# PowerOn.net
KiCad netlist of a schematic drawn in EAGLE
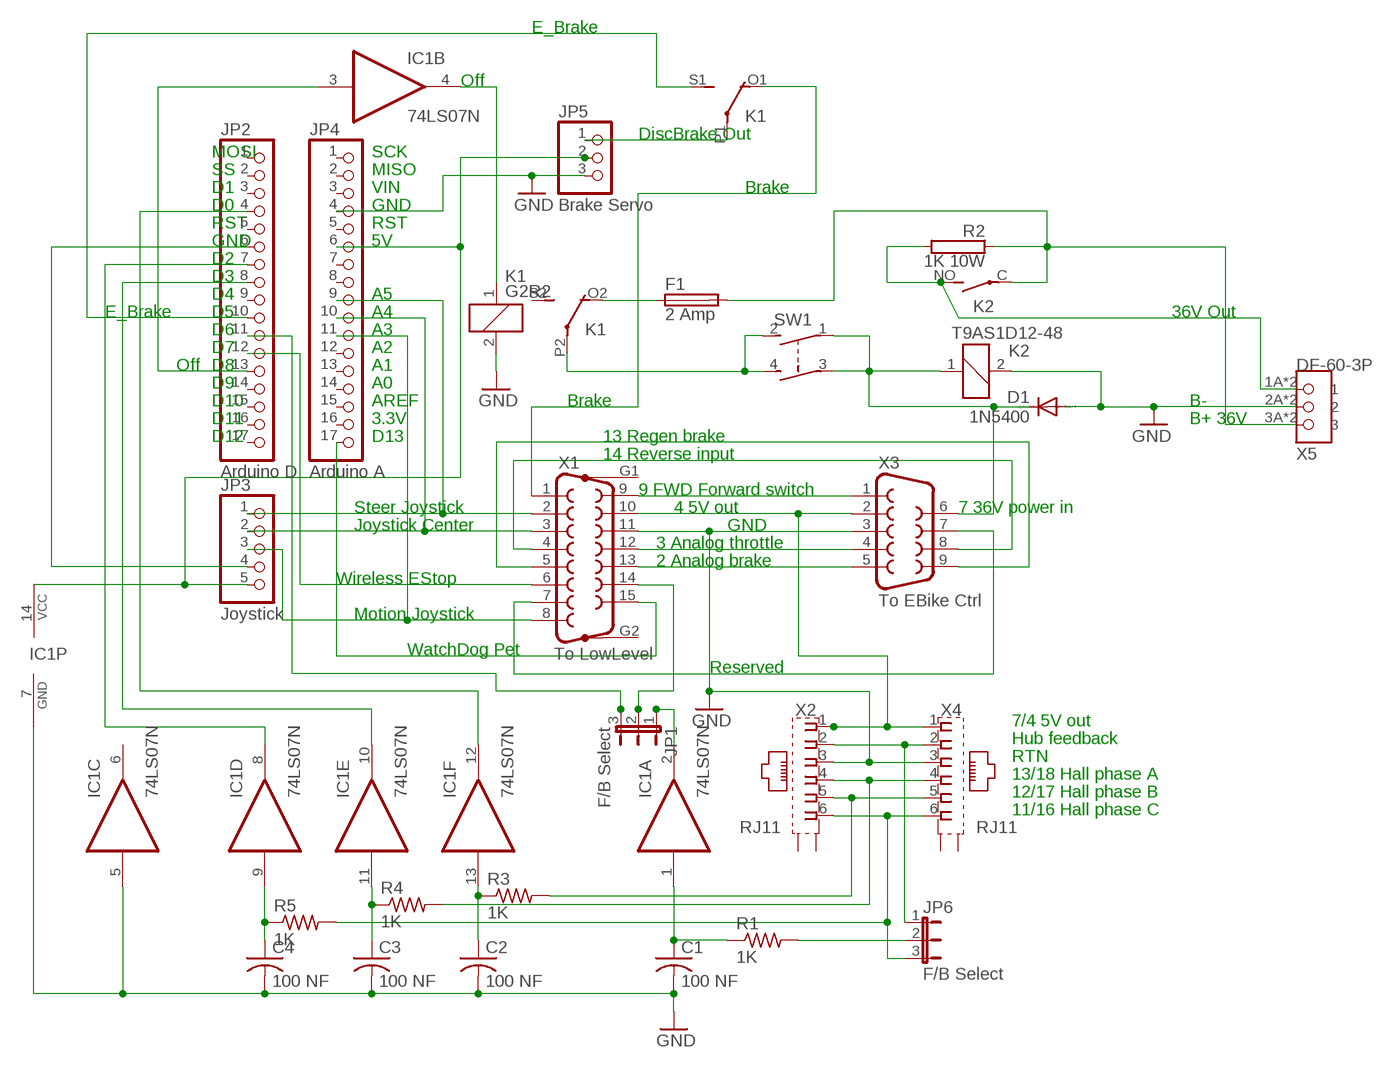
[diagram p0: schematic, sheet 1]

(export (version "E")
  (design (tool "Eeschema 10.0.6"))
  (components
    (comp (ref "C1")
      (value "100 NF")
      (footprint "eagle-import:C050-050X075")
      (libsource (lib "eagle-import") (part "C-US050-050X075"))
    )
    (comp (ref "C2")
      (value "100 NF")
      (footprint "eagle-import:C050-024X044")
      (libsource (lib "eagle-import") (part "C-US050-024X044"))
    )
    (comp (ref "C3")
      (value "100 NF")
      (footprint "eagle-import:C050-024X044")
      (libsource (lib "eagle-import") (part "C-US050-024X044"))
    )
    (comp (ref "C4")
      (value "100 NF")
      (footprint "eagle-import:C050-024X044")
      (libsource (lib "eagle-import") (part "C-US050-024X044"))
    )
    (comp (ref "D1")
      (value "1N5400")
      (footprint "eagle-import:DO201-15")
      (libsource (lib "eagle-import") (part "1N5400"))
    )
    (comp (ref "F1")
      (value "2 Amp")
      (footprint "eagle-import:SH22,5")
      (fields (field (name "MF") "SCHURTER") (field (name "MPN") "0031.8201"))
      (libsource (lib "eagle-import") (part "SH22,5"))
    )
    (comp (ref "IC1")
      (value "74LS07N")
      (footprint "eagle-import:DIL14")
      (libsource (lib "eagle-import") (part "7407NLS"))
    )
    (comp (ref "JP1")
      (value "F/B Select")
      (footprint "eagle-import:JP2")
      (libsource (lib "eagle-import") (part "JP2E"))
    )
    (comp (ref "JP2")
      (value "Arduino D")
      (footprint "eagle-import:1X17")
      (libsource (lib "eagle-import") (part "PINHD-1X17"))
    )
    (comp (ref "JP3")
      (value "Joystick")
      (footprint "eagle-import:1X05_90")
      (libsource (lib "eagle-import") (part "PINHD-1X5/90"))
    )
    (comp (ref "JP4")
      (value "Arduino A")
      (footprint "eagle-import:1X17")
      (libsource (lib "eagle-import") (part "PINHD-1X17"))
    )
    (comp (ref "JP5")
      (value "Brake Servo")
      (footprint "eagle-import:1X03_90")
      (libsource (lib "eagle-import") (part "PINHD-1X3/90"))
    )
    (comp (ref "JP6")
      (value "F/B Select")
      (footprint "eagle-import:JP2")
      (libsource (lib "eagle-import") (part "JP2E"))
    )
    (comp (ref "K1")
      (value "G2R2")
      (footprint "eagle-import:G2R2")
      (fields (field (name "MF") "OMRON COMPONENTS USA") (field (name "MPN") "G2R-2-DC6"))
      (libsource (lib "eagle-import") (part "G2R2"))
    )
    (comp (ref "K2")
      (value "T9AS1D12-48")
      (footprint "eagle-import:JT1A-PCB")
      (libsource (lib "eagle-import") (part "JT1A?--PCBDC24V"))
    )
    (comp (ref "R1")
      (value "1K")
      (footprint "eagle-import:0411_15")
      (libsource (lib "eagle-import") (part "R-US_0411/15"))
    )
    (comp (ref "R2")
      (value "1K 10W")
      (footprint "eagle-import:AC07")
      (libsource (lib "eagle-import") (part "RAC07"))
    )
    (comp (ref "R3")
      (value "1K")
      (footprint "eagle-import:0207_10")
      (libsource (lib "eagle-import") (part "R-US_0207/10"))
    )
    (comp (ref "R4")
      (value "1K")
      (footprint "eagle-import:0207_10")
      (libsource (lib "eagle-import") (part "R-US_0207/10"))
    )
    (comp (ref "R5")
      (value "1K")
      (footprint "eagle-import:0207_10")
      (libsource (lib "eagle-import") (part "R-US_0207/10"))
    )
    (comp (ref "SW1")
      (value "CK-S201")
      (footprint "eagle-import:CK-S201")
      (libsource (lib "eagle-import") (part "CK-S201"))
    )
    (comp (ref "X1")
      (value "To LowLevel")
      (footprint "eagle-import:F15HP")
      (libsource (lib "eagle-import") (part "F15HP"))
    )
    (comp (ref "X2")
      (value "RJ11")
      (footprint "eagle-import:XRJK-S-01-6-6-0-2G2-NO")
      (libsource (lib "eagle-import") (part "XRJK6-0-2G2-NO-S-01-6-"))
    )
    (comp (ref "X3")
      (value "To EBike Ctrl")
      (footprint "eagle-import:F09H")
      (libsource (lib "eagle-import") (part "F09H"))
    )
    (comp (ref "X4")
      (value "RJ11")
      (footprint "eagle-import:XRJK-S-01-6-6-0-2G2-NO")
      (libsource (lib "eagle-import") (part "XRJK6-0-2G2-NO-S-01-6-"))
    )
    (comp (ref "X5")
      (value "HIROSE-DF60-3P-10.16DSA")
      (footprint "eagle-import:DF-60-3P-10.16")
      (libsource (lib "eagle-import") (part "HIROSE-DF60-3P-10.16DSA"))
    )
  )
  (nets
    (net (code "1") (name "GND") (class "Default")
      (node (ref "C1") (pin "2") (pinfunction "2_2") (pintype "passive"))
      (node (ref "C2") (pin "2") (pinfunction "2_2") (pintype "passive"))
      (node (ref "C3") (pin "2") (pinfunction "2_2") (pintype "passive"))
      (node (ref "C4") (pin "2") (pinfunction "2_2") (pintype "passive"))
      (node (ref "D1") (pin "A") (pinfunction "A_A") (pintype "passive"))
      (node (ref "IC1") (pin "5") (pinfunction "I_5") (pintype "input"))
      (node (ref "IC1") (pin "7") (pinfunction "GND_7") (pintype "power_in"))
      (node (ref "JP4") (pin "4") (pinfunction "4_4") (pintype "passive"))
      (node (ref "JP5") (pin "3") (pinfunction "3_3") (pintype "passive"))
      (node (ref "K1") (pin "2") (pinfunction "2_2") (pintype "passive"))
      (node (ref "K2") (pin "2") (pinfunction "2_2") (pintype "passive"))
      (node (ref "X1") (pin "11") (pinfunction "11_11") (pintype "passive"))
      (node (ref "X2") (pin "3") (pinfunction "3_3") (pintype "passive"))
      (node (ref "X3") (pin "3") (pinfunction "3_3") (pintype "passive"))
      (node (ref "X4") (pin "3") (pinfunction "3_3") (pintype "passive"))
      (node (ref "X5") (pin "2A") (pinfunction "2_2A") (pintype "passive"))
      (node (ref "X5") (pin "2B") (pinfunction "2_2B") (pintype "passive"))
    )
    (net (code "2") (name "Net-(IC1A-I)") (class "Default")
      (node (ref "C1") (pin "1") (pinfunction "1_1") (pintype "passive"))
      (node (ref "IC1") (pin "1") (pinfunction "I_1") (pintype "input"))
      (node (ref "R1") (pin "1") (pinfunction "1_1") (pintype "passive"))
    )
    (net (code "3") (name "Net-(IC1A-O)") (class "Default")
      (node (ref "IC1") (pin "2") (pinfunction "O_2") (pintype "open_collector"))
      (node (ref "JP1") (pin "1") (pinfunction "1_1") (pintype "passive"))
    )
    (net (code "4") (name "Net-(IC1B-I)") (class "Default")
      (node (ref "IC1") (pin "3") (pinfunction "I_3") (pintype "input"))
      (node (ref "JP2") (pin "13") (pinfunction "13_13") (pintype "passive"))
    )
    (net (code "5") (name "Net-(IC1B-O)") (class "Default")
      (node (ref "IC1") (pin "4") (pinfunction "O_4") (pintype "open_collector"))
      (node (ref "K1") (pin "1") (pinfunction "1_1") (pintype "passive"))
    )
    (net (code "6") (name "Net-(IC1D-I)") (class "Default")
      (node (ref "C4") (pin "1") (pinfunction "1_1") (pintype "passive"))
      (node (ref "IC1") (pin "9") (pinfunction "I_9") (pintype "input"))
      (node (ref "R5") (pin "1") (pinfunction "1_1") (pintype "passive"))
    )
    (net (code "7") (name "Net-(IC1D-O)") (class "Default")
      (node (ref "IC1") (pin "8") (pinfunction "O_8") (pintype "open_collector"))
      (node (ref "JP2") (pin "7") (pinfunction "7_7") (pintype "passive"))
    )
    (net (code "8") (name "Net-(IC1E-I)") (class "Default")
      (node (ref "C3") (pin "1") (pinfunction "1_1") (pintype "passive"))
      (node (ref "IC1") (pin "11") (pinfunction "I_11") (pintype "input"))
      (node (ref "R4") (pin "1") (pinfunction "1_1") (pintype "passive"))
    )
    (net (code "9") (name "Net-(IC1E-O)") (class "Default")
      (node (ref "IC1") (pin "10") (pinfunction "O_10") (pintype "open_collector"))
      (node (ref "JP2") (pin "8") (pinfunction "8_8") (pintype "passive"))
    )
    (net (code "10") (name "Net-(IC1F-I)") (class "Default")
      (node (ref "C2") (pin "1") (pinfunction "1_1") (pintype "passive"))
      (node (ref "IC1") (pin "13") (pinfunction "I_13") (pintype "input"))
      (node (ref "R3") (pin "1") (pinfunction "1_1") (pintype "passive"))
    )
    (net (code "11") (name "Net-(IC1F-O)") (class "Default")
      (node (ref "IC1") (pin "12") (pinfunction "O_12") (pintype "open_collector"))
      (node (ref "JP2") (pin "4") (pinfunction "4_4") (pintype "passive"))
    )
    (net (code "12") (name "Net-(IC1G-VCC)") (class "Default")
      (node (ref "IC1") (pin "14") (pinfunction "VCC_14") (pintype "power_in"))
      (node (ref "JP3") (pin "5") (pinfunction "5_5") (pintype "passive"))
      (node (ref "JP4") (pin "6") (pinfunction "6_6") (pintype "passive"))
      (node (ref "JP5") (pin "2") (pinfunction "2_2") (pintype "passive"))
    )
    (net (code "13") (name "Net-(JP1-Pad2)") (class "Default")
      (node (ref "JP1") (pin "2") (pinfunction "2_2") (pintype "passive"))
      (node (ref "X1") (pin "14") (pinfunction "14_14") (pintype "passive"))
    )
    (net (code "14") (name "Net-(JP1-Pad3)") (class "Default")
      (node (ref "JP1") (pin "3") (pinfunction "3_3") (pintype "passive"))
      (node (ref "JP2") (pin "11") (pinfunction "11_11") (pintype "passive"))
    )
    (net (code "15") (name "Net-(JP2-Pad6)") (class "Default")
      (node (ref "JP2") (pin "6") (pinfunction "6_6") (pintype "passive"))
      (node (ref "JP3") (pin "4") (pinfunction "4_4") (pintype "passive"))
    )
    (net (code "16") (name "Net-(JP2-Pad12)") (class "Default")
      (node (ref "JP2") (pin "12") (pinfunction "12_12") (pintype "passive"))
      (node (ref "X1") (pin "6") (pinfunction "6_6") (pintype "passive"))
    )
    (net (code "17") (name "Net-(JP3-Pad1)") (class "Default")
      (node (ref "JP3") (pin "1") (pinfunction "1_1") (pintype "passive"))
      (node (ref "JP4") (pin "9") (pinfunction "9_9") (pintype "passive"))
      (node (ref "X1") (pin "2") (pinfunction "2_2") (pintype "passive"))
    )
    (net (code "18") (name "Net-(JP3-Pad2)") (class "Default")
      (node (ref "JP3") (pin "2") (pinfunction "2_2") (pintype "passive"))
      (node (ref "JP4") (pin "10") (pinfunction "10_10") (pintype "passive"))
      (node (ref "X1") (pin "3") (pinfunction "3_3") (pintype "passive"))
    )
    (net (code "19") (name "Net-(JP3-Pad3)") (class "Default")
      (node (ref "JP3") (pin "3") (pinfunction "3_3") (pintype "passive"))
      (node (ref "JP4") (pin "11") (pinfunction "11_11") (pintype "passive"))
      (node (ref "X1") (pin "8") (pinfunction "8_8") (pintype "passive"))
    )
    (net (code "20") (name "Net-(JP4-Pad17)") (class "Default")
      (node (ref "JP4") (pin "17") (pinfunction "17_17") (pintype "passive"))
      (node (ref "X1") (pin "15") (pinfunction "15_15") (pintype "passive"))
    )
    (net (code "21") (name "Net-(JP6-Pad1)") (class "Default")
      (node (ref "JP6") (pin "1") (pinfunction "1_1") (pintype "passive"))
      (node (ref "X2") (pin "2") (pinfunction "2_2") (pintype "passive"))
      (node (ref "X4") (pin "2") (pinfunction "2_2") (pintype "passive"))
    )
    (net (code "22") (name "Net-(JP6-Pad2)") (class "Default")
      (node (ref "JP6") (pin "2") (pinfunction "2_2") (pintype "passive"))
      (node (ref "R1") (pin "2") (pinfunction "2_2") (pintype "passive"))
    )
    (net (code "23") (name "Net-(JP6-Pad3)") (class "Default")
      (node (ref "JP6") (pin "3") (pinfunction "3_3") (pintype "passive"))
      (node (ref "R5") (pin "2") (pinfunction "2_2") (pintype "passive"))
      (node (ref "X2") (pin "6") (pinfunction "6_6") (pintype "passive"))
      (node (ref "X4") (pin "6") (pinfunction "6_6") (pintype "passive"))
    )
    (net (code "24") (name "Net-(K1B-O)") (class "Default")
      (node (ref "K1") (pin "O1") (pinfunction "O_O1") (pintype "passive"))
      (node (ref "X1") (pin "1") (pinfunction "1_1") (pintype "passive"))
    )
    (net (code "25") (name "Net-(K1B-P)") (class "Default")
      (node (ref "JP5") (pin "1") (pinfunction "1_1") (pintype "passive"))
      (node (ref "K1") (pin "P1") (pinfunction "P_P1") (pintype "passive"))
    )
    (net (code "26") (name "Net-(K1B-S)") (class "Default")
      (node (ref "JP2") (pin "10") (pinfunction "10_10") (pintype "passive"))
      (node (ref "K1") (pin "S1") (pinfunction "S_S1") (pintype "passive"))
    )
    (net (code "27") (name "Net-(K1C-O)") (class "Default")
      (node (ref "F1") (pin "1") (pinfunction "1_1") (pintype "passive"))
      (node (ref "K1") (pin "O2") (pinfunction "O_O2") (pintype "passive"))
    )
    (net (code "28") (name "Net-(K1C-P)") (class "Default")
      (node (ref "K1") (pin "P2") (pinfunction "P_P2") (pintype "passive"))
      (node (ref "SW1") (pin "2") (pinfunction "S_2") (pintype "passive"))
      (node (ref "SW1") (pin "4") (pinfunction "S1_4") (pintype "passive"))
    )
    (net (code "29") (name "Net-(K2B-P)") (class "Default")
      (node (ref "F1") (pin "2") (pinfunction "2_2") (pintype "passive"))
      (node (ref "K2") (pin "C") (pinfunction "P_C") (pintype "passive"))
      (node (ref "R2") (pin "1") (pinfunction "1_1") (pintype "passive"))
      (node (ref "X5") (pin "3A") (pinfunction "3_3A") (pintype "passive"))
      (node (ref "X5") (pin "3B") (pinfunction "3_3B") (pintype "passive"))
    )
    (net (code "30") (name "Net-(K2B-S)") (class "Default")
      (node (ref "K2") (pin "NO") (pinfunction "S_NO") (pintype "passive"))
      (node (ref "R2") (pin "2") (pinfunction "2_2") (pintype "passive"))
      (node (ref "X5") (pin "1A") (pinfunction "1_1A") (pintype "passive"))
      (node (ref "X5") (pin "1B") (pinfunction "1_1B") (pintype "passive"))
    )
    (net (code "31") (name "Net-(R3-Pad2)") (class "Default")
      (node (ref "R3") (pin "2") (pinfunction "2_2") (pintype "passive"))
      (node (ref "X2") (pin "5") (pinfunction "5_5") (pintype "passive"))
      (node (ref "X4") (pin "5") (pinfunction "5_5") (pintype "passive"))
    )
    (net (code "32") (name "Net-(R4-Pad2)") (class "Default")
      (node (ref "R4") (pin "2") (pinfunction "2_2") (pintype "passive"))
      (node (ref "X2") (pin "4") (pinfunction "4_4") (pintype "passive"))
      (node (ref "X4") (pin "4") (pinfunction "4_4") (pintype "passive"))
    )
    (net (code "33") (name "Net-(SW1-P)") (class "Default")
      (node (ref "D1") (pin "C") (pinfunction "C_C") (pintype "passive"))
      (node (ref "K2") (pin "1") (pinfunction "1_1") (pintype "passive"))
      (node (ref "SW1") (pin "1") (pinfunction "P_1") (pintype "passive"))
      (node (ref "SW1") (pin "3") (pinfunction "P1_3") (pintype "passive"))
      (node (ref "X3") (pin "6") (pinfunction "6_6") (pintype "passive"))
    )
    (net (code "34") (name "Net-(X1-Pad4)") (class "Default")
      (node (ref "X1") (pin "4") (pinfunction "4_4") (pintype "passive"))
      (node (ref "X3") (pin "8") (pinfunction "8_8") (pintype "passive"))
    )
    (net (code "35") (name "Net-(X1-Pad5)") (class "Default")
      (node (ref "X1") (pin "5") (pinfunction "5_5") (pintype "passive"))
      (node (ref "X3") (pin "9") (pinfunction "9_9") (pintype "passive"))
    )
    (net (code "36") (name "Net-(X1-Pad7)") (class "Default")
      (node (ref "X1") (pin "7") (pinfunction "7_7") (pintype "passive"))
      (node (ref "X3") (pin "7") (pinfunction "7_7") (pintype "passive"))
    )
    (net (code "37") (name "Net-(X1-Pad9)") (class "Default")
      (node (ref "X1") (pin "9") (pinfunction "9_9") (pintype "passive"))
      (node (ref "X3") (pin "1") (pinfunction "1_1") (pintype "passive"))
    )
    (net (code "38") (name "Net-(X1-Pad10)") (class "Default")
      (node (ref "X1") (pin "10") (pinfunction "10_10") (pintype "passive"))
      (node (ref "X2") (pin "1") (pinfunction "1_1") (pintype "passive"))
      (node (ref "X3") (pin "2") (pinfunction "2_2") (pintype "passive"))
      (node (ref "X4") (pin "1") (pinfunction "1_1") (pintype "passive"))
    )
    (net (code "39") (name "Net-(X1-Pad12)") (class "Default")
      (node (ref "X1") (pin "12") (pinfunction "12_12") (pintype "passive"))
      (node (ref "X3") (pin "4") (pinfunction "4_4") (pintype "passive"))
    )
    (net (code "40") (name "Net-(X1-Pad13)") (class "Default")
      (node (ref "X1") (pin "13") (pinfunction "13_13") (pintype "passive"))
      (node (ref "X3") (pin "5") (pinfunction "5_5") (pintype "passive"))
    )
    (net (code "41") (name "unconnected-(IC1C-O-Pad6)") (class "Default")
      (node (ref "IC1") (pin "6") (pinfunction "O_6") (pintype "open_collector"))
    )
    (net (code "42") (name "unconnected-(JP2-Pad1)") (class "Default")
      (node (ref "JP2") (pin "1") (pinfunction "1_1") (pintype "passive"))
    )
    (net (code "43") (name "unconnected-(JP2-Pad2)") (class "Default")
      (node (ref "JP2") (pin "2") (pinfunction "2_2") (pintype "passive"))
    )
    (net (code "44") (name "unconnected-(JP2-Pad3)") (class "Default")
      (node (ref "JP2") (pin "3") (pinfunction "3_3") (pintype "passive"))
    )
    (net (code "45") (name "unconnected-(JP2-Pad5)") (class "Default")
      (node (ref "JP2") (pin "5") (pinfunction "5_5") (pintype "passive"))
    )
    (net (code "46") (name "unconnected-(JP2-Pad9)") (class "Default")
      (node (ref "JP2") (pin "9") (pinfunction "9_9") (pintype "passive"))
    )
    (net (code "47") (name "unconnected-(JP2-Pad14)") (class "Default")
      (node (ref "JP2") (pin "14") (pinfunction "14_14") (pintype "passive"))
    )
    (net (code "48") (name "unconnected-(JP2-Pad15)") (class "Default")
      (node (ref "JP2") (pin "15") (pinfunction "15_15") (pintype "passive"))
    )
    (net (code "49") (name "unconnected-(JP2-Pad16)") (class "Default")
      (node (ref "JP2") (pin "16") (pinfunction "16_16") (pintype "passive"))
    )
    (net (code "50") (name "unconnected-(JP2-Pad17)") (class "Default")
      (node (ref "JP2") (pin "17") (pinfunction "17_17") (pintype "passive"))
    )
    (net (code "51") (name "unconnected-(JP4-Pad1)") (class "Default")
      (node (ref "JP4") (pin "1") (pinfunction "1_1") (pintype "passive"))
    )
    (net (code "52") (name "unconnected-(JP4-Pad2)") (class "Default")
      (node (ref "JP4") (pin "2") (pinfunction "2_2") (pintype "passive"))
    )
    (net (code "53") (name "unconnected-(JP4-Pad3)") (class "Default")
      (node (ref "JP4") (pin "3") (pinfunction "3_3") (pintype "passive"))
    )
    (net (code "54") (name "unconnected-(JP4-Pad5)") (class "Default")
      (node (ref "JP4") (pin "5") (pinfunction "5_5") (pintype "passive"))
    )
    (net (code "55") (name "unconnected-(JP4-Pad7)") (class "Default")
      (node (ref "JP4") (pin "7") (pinfunction "7_7") (pintype "passive"))
    )
    (net (code "56") (name "unconnected-(JP4-Pad8)") (class "Default")
      (node (ref "JP4") (pin "8") (pinfunction "8_8") (pintype "passive"))
    )
    (net (code "57") (name "unconnected-(JP4-Pad12)") (class "Default")
      (node (ref "JP4") (pin "12") (pinfunction "12_12") (pintype "passive"))
    )
    (net (code "58") (name "unconnected-(JP4-Pad13)") (class "Default")
      (node (ref "JP4") (pin "13") (pinfunction "13_13") (pintype "passive"))
    )
    (net (code "59") (name "unconnected-(JP4-Pad14)") (class "Default")
      (node (ref "JP4") (pin "14") (pinfunction "14_14") (pintype "passive"))
    )
    (net (code "60") (name "unconnected-(JP4-Pad15)") (class "Default")
      (node (ref "JP4") (pin "15") (pinfunction "15_15") (pintype "passive"))
    )
    (net (code "61") (name "unconnected-(JP4-Pad16)") (class "Default")
      (node (ref "JP4") (pin "16") (pinfunction "16_16") (pintype "passive"))
    )
    (net (code "62") (name "unconnected-(K1C-S-PadS2)") (class "Default")
      (node (ref "K1") (pin "S2") (pinfunction "S_S2") (pintype "passive"))
    )
    (net (code "63") (name "unconnected-(X1-PadG1)") (class "Default")
      (node (ref "X1") (pin "G1") (pinfunction "G1_G1") (pintype "passive"))
    )
    (net (code "64") (name "unconnected-(X1-PadG2)") (class "Default")
      (node (ref "X1") (pin "G2") (pinfunction "G2_G2") (pintype "passive"))
    )
    (net (code "65") (name "unconnected-(X2-S-PadS1)") (class "Default")
      (node (ref "X2") (pin "S1") (pinfunction "S_S1") (pintype "passive"))
    )
    (net (code "66") (name "unconnected-(X2-S-PadS2)") (class "Default")
      (node (ref "X2") (pin "S2") (pinfunction "S_S2") (pintype "passive"))
    )
    (net (code "67") (name "unconnected-(X4-S-PadS1)") (class "Default")
      (node (ref "X4") (pin "S1") (pinfunction "S_S1") (pintype "passive"))
    )
    (net (code "68") (name "unconnected-(X4-S-PadS2)") (class "Default")
      (node (ref "X4") (pin "S2") (pinfunction "S_S2") (pintype "passive"))
    )
  )
)
